# FaultOptoNO.net
KiCad netlist of a schematic drawn in Altium Designer
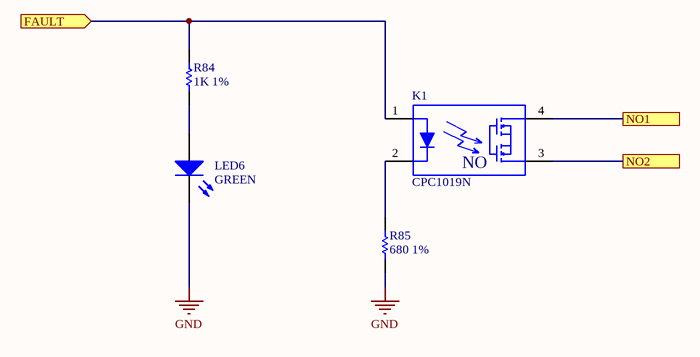
[diagram p0: FaultOptoNO.SchDoc]

(export (version "E")
  (design (tool "Eeschema 10.0.6"))
  (components
    (comp (ref "K1")
      (value "CPC1019N")
      (footprint "MC1:SOP254P610X206-4N")
      (description "Relay SSR 50mA 1.4V DC-IN 0.75A 60V AC-OUT 4-Pin SOP Tube")
      (fields (field (name "MANUFACTURER") "Ixys Clare"))
      (libsource (lib "MC1") (part "CPC1019N"))
    )
    (comp (ref "LED6")
      (value "GREEN")
      (footprint "LED0805")
      (description "LED GREEN CLEAR 0805 SMD")
      (fields
        (field (name "MANUFACTURER") "Wurth Electronics")
        (field (name "MANUFACTURER PART NUMBER") "150080VS75000")
      )
      (libsource (lib "MCx") (part "150080VS75000"))
    )
    (comp (ref "R84")
      (value "1K 1%")
      (footprint "R0805")
      (fields
        (field (name "MANUFACTURER") "Yageo")
        (field (name "MANUFACTURER PART NUMBER") "RC0805FR-071KL")
        (field (name "TOLERANCE") "1%")
      )
      (libsource (lib "MCx") (part "RC0805FR-071KL"))
    )
    (comp (ref "R85")
      (value "680 1%")
      (footprint "R0805")
      (fields
        (field (name "MANUFACTURER") "Panasonic")
        (field (name "MANUFACTURER PART NUMBER") "ERJ6ENF6800V")
        (field (name "TOLERANCE") "1%")
      )
      (libsource (lib "MCx") (part "ERJ6ENF6800V"))
    )
  )
  (nets
    (net (code "1") (name "/FAULT") (class "Default")
      (node (ref "K1") (pin "1") (pinfunction "1_1") (pintype "passive"))
      (node (ref "R84") (pin "1") (pinfunction "1_1") (pintype "passive"))
    )
    (net (code "2") (name "/NO1") (class "Default")
      (node (ref "K1") (pin "4") (pinfunction "4_4") (pintype "passive"))
    )
    (net (code "3") (name "/NO2") (class "Default")
      (node (ref "K1") (pin "3") (pinfunction "3_3") (pintype "passive"))
    )
    (net (code "4") (name "GND") (class "Default")
      (node (ref "LED6") (pin "1") (pinfunction "K_1") (pintype "passive"))
      (node (ref "R85") (pin "1") (pinfunction "1_1") (pintype "passive"))
    )
    (net (code "5") (name "Net-(K1-Pad2)") (class "Default")
      (node (ref "K1") (pin "2") (pinfunction "2_2") (pintype "passive"))
      (node (ref "R85") (pin "2") (pinfunction "2_2") (pintype "passive"))
    )
    (net (code "6") (name "Net-(LED6-A)") (class "Default")
      (node (ref "LED6") (pin "2") (pinfunction "A_2") (pintype "passive"))
      (node (ref "R84") (pin "2") (pinfunction "2_2") (pintype "passive"))
    )
  )
)
